# SPT3G_AdapterBoard.net
KiCad netlist of a schematic drawn in Altium Designer
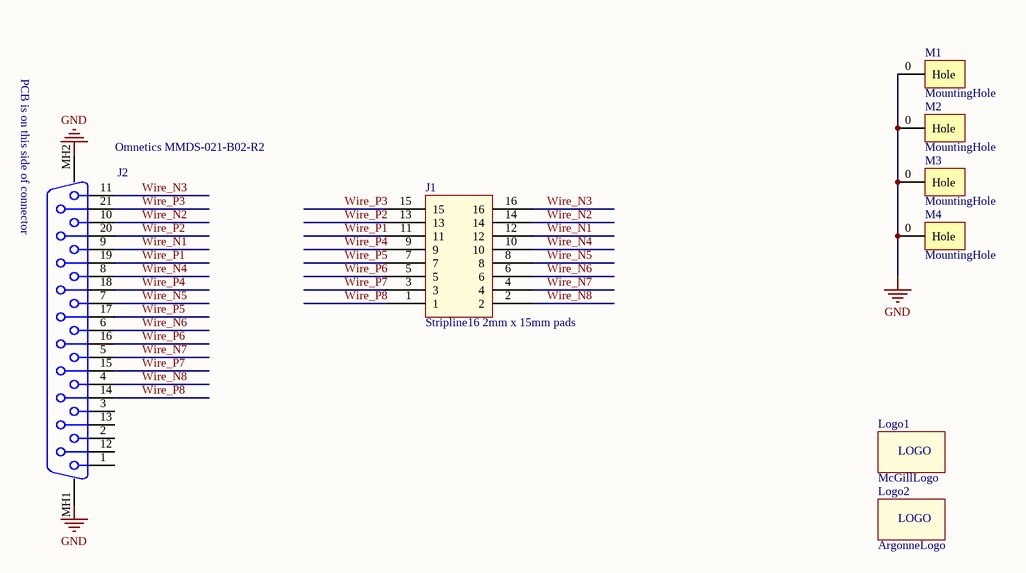
[diagram p0: SPT3G_AdapterBoard.SchDoc]

(export (version "E")
  (design (tool "Eeschema 10.0.6"))
  (components
    (comp (ref "J1")
      (value "Stripline16 2mm x 15mm pads")
      (footprint "Stripline16")
      (libsource (lib "SPT3G_AdapterBoard") (part "Stripline16"))
    )
    (comp (ref "J2")
      (value "Omnetics MMDS-021-B02-R2")
      (footprint "MMDS-021-B02-R2")
      (description "OmneticsMicroD21")
      (libsource (lib "SPT3G_LCBoard") (part "OmneticsMicroD21"))
    )
    (comp (ref "Logo1")
      (value "McGillLogo")
      (footprint "McGillLogo1")
      (libsource (lib "SPT3G_AdapterBoard") (part "Logo"))
    )
    (comp (ref "Logo2")
      (value "ArgonneLogo")
      (footprint "ArgonneLogo")
      (libsource (lib "SPT3G_AdapterBoard") (part "Logo"))
    )
    (comp (ref "M1")
      (value "MountingHole")
      (footprint "MountingHole")
      (libsource (lib "SPT3G_AdapterBoard") (part "MountingHole"))
    )
    (comp (ref "M2")
      (value "MountingHole")
      (footprint "MountingHole")
      (libsource (lib "SPT3G_AdapterBoard") (part "MountingHole"))
    )
    (comp (ref "M3")
      (value "MountingHole")
      (footprint "MountingHole")
      (libsource (lib "SPT3G_AdapterBoard") (part "MountingHole"))
    )
    (comp (ref "M4")
      (value "MountingHole")
      (footprint "MountingHole")
      (libsource (lib "SPT3G_AdapterBoard") (part "MountingHole"))
    )
  )
  (nets
    (net (code "1") (name "/Wire_N1") (class "Default")
      (node (ref "J1") (pin "12") (pinfunction "12_12") (pintype "passive"))
      (node (ref "J2") (pin "9") (pinfunction "9_9") (pintype "passive"))
    )
    (net (code "2") (name "/Wire_N2") (class "Default")
      (node (ref "J1") (pin "14") (pinfunction "14_14") (pintype "passive"))
      (node (ref "J2") (pin "10") (pinfunction "10_10") (pintype "passive"))
    )
    (net (code "3") (name "/Wire_N3") (class "Default")
      (node (ref "J1") (pin "16") (pinfunction "16_16") (pintype "passive"))
      (node (ref "J2") (pin "11") (pinfunction "11_11") (pintype "passive"))
    )
    (net (code "4") (name "/Wire_N4") (class "Default")
      (node (ref "J1") (pin "10") (pinfunction "10_10") (pintype "passive"))
      (node (ref "J2") (pin "8") (pinfunction "8_8") (pintype "passive"))
    )
    (net (code "5") (name "/Wire_N5") (class "Default")
      (node (ref "J1") (pin "8") (pinfunction "8_8") (pintype "passive"))
      (node (ref "J2") (pin "7") (pinfunction "7_7") (pintype "passive"))
    )
    (net (code "6") (name "/Wire_N6") (class "Default")
      (node (ref "J1") (pin "6") (pinfunction "6_6") (pintype "passive"))
      (node (ref "J2") (pin "6") (pinfunction "6_6") (pintype "passive"))
    )
    (net (code "7") (name "/Wire_N7") (class "Default")
      (node (ref "J1") (pin "4") (pinfunction "4_4") (pintype "passive"))
      (node (ref "J2") (pin "5") (pinfunction "5_5") (pintype "passive"))
    )
    (net (code "8") (name "/Wire_N8") (class "Default")
      (node (ref "J1") (pin "2") (pinfunction "2_2") (pintype "passive"))
      (node (ref "J2") (pin "4") (pinfunction "4_4") (pintype "passive"))
    )
    (net (code "9") (name "/Wire_P1") (class "Default")
      (node (ref "J1") (pin "11") (pinfunction "11_11") (pintype "passive"))
      (node (ref "J2") (pin "19") (pinfunction "19_19") (pintype "passive"))
    )
    (net (code "10") (name "/Wire_P2") (class "Default")
      (node (ref "J1") (pin "13") (pinfunction "13_13") (pintype "passive"))
      (node (ref "J2") (pin "20") (pinfunction "20_20") (pintype "passive"))
    )
    (net (code "11") (name "/Wire_P3") (class "Default")
      (node (ref "J1") (pin "15") (pinfunction "15_15") (pintype "passive"))
      (node (ref "J2") (pin "21") (pinfunction "21_21") (pintype "passive"))
    )
    (net (code "12") (name "/Wire_P4") (class "Default")
      (node (ref "J1") (pin "9") (pinfunction "9_9") (pintype "passive"))
      (node (ref "J2") (pin "18") (pinfunction "18_18") (pintype "passive"))
    )
    (net (code "13") (name "/Wire_P5") (class "Default")
      (node (ref "J1") (pin "7") (pinfunction "7_7") (pintype "passive"))
      (node (ref "J2") (pin "17") (pinfunction "17_17") (pintype "passive"))
    )
    (net (code "14") (name "/Wire_P6") (class "Default")
      (node (ref "J1") (pin "5") (pinfunction "5_5") (pintype "passive"))
      (node (ref "J2") (pin "16") (pinfunction "16_16") (pintype "passive"))
    )
    (net (code "15") (name "/Wire_P7") (class "Default")
      (node (ref "J1") (pin "3") (pinfunction "3_3") (pintype "passive"))
      (node (ref "J2") (pin "15") (pinfunction "15_15") (pintype "passive"))
    )
    (net (code "16") (name "/Wire_P8") (class "Default")
      (node (ref "J1") (pin "1") (pinfunction "1_1") (pintype "passive"))
      (node (ref "J2") (pin "14") (pinfunction "14_14") (pintype "passive"))
    )
    (net (code "17") (name "GND") (class "Default")
      (node (ref "J2") (pin "MH1") (pinfunction "MH1_MH1") (pintype "passive"))
      (node (ref "J2") (pin "MH2") (pinfunction "MH2_MH2") (pintype "passive"))
      (node (ref "M1") (pin "0") (pinfunction "Hole_0") (pintype "passive"))
      (node (ref "M2") (pin "0") (pinfunction "Hole_0") (pintype "passive"))
      (node (ref "M3") (pin "0") (pinfunction "Hole_0") (pintype "passive"))
      (node (ref "M4") (pin "0") (pinfunction "Hole_0") (pintype "passive"))
    )
    (net (code "18") (name "unconnected-(J2-Pad1)") (class "Default")
      (node (ref "J2") (pin "1") (pinfunction "1_1") (pintype "passive"))
    )
    (net (code "19") (name "unconnected-(J2-Pad2)") (class "Default")
      (node (ref "J2") (pin "2") (pinfunction "2_2") (pintype "passive"))
    )
    (net (code "20") (name "unconnected-(J2-Pad3)") (class "Default")
      (node (ref "J2") (pin "3") (pinfunction "3_3") (pintype "passive"))
    )
    (net (code "21") (name "unconnected-(J2-Pad12)") (class "Default")
      (node (ref "J2") (pin "12") (pinfunction "12_12") (pintype "passive"))
    )
    (net (code "22") (name "unconnected-(J2-Pad13)") (class "Default")
      (node (ref "J2") (pin "13") (pinfunction "13_13") (pintype "passive"))
    )
  )
)
